# com-uart.net
KiCad netlist of a schematic drawn in EAGLE
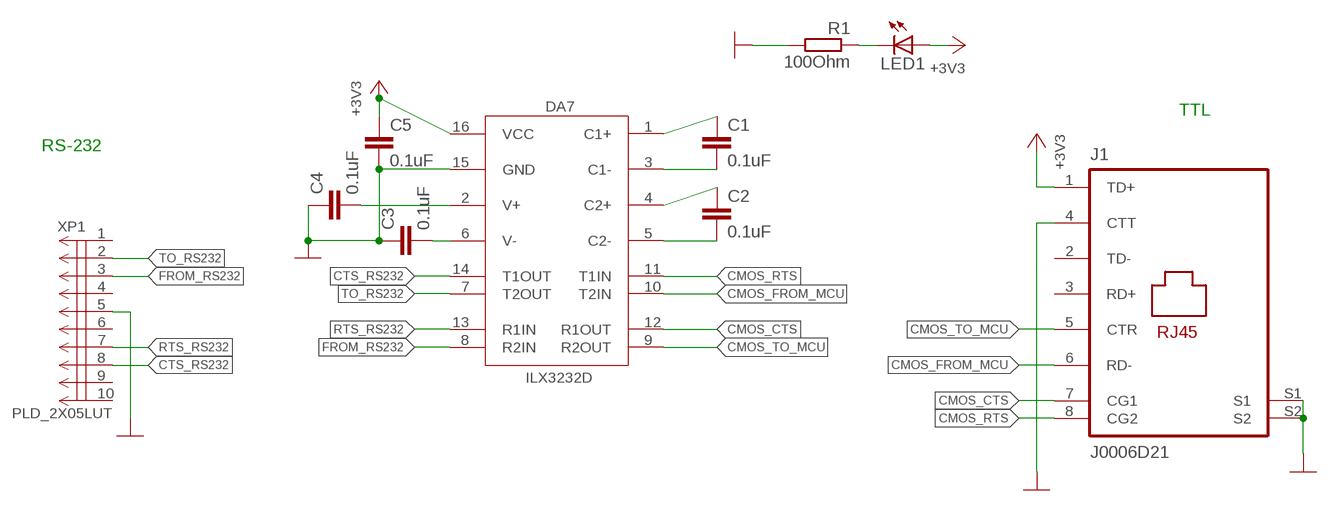
[diagram p0: schematic, sheet 1]

(export (version "E")
  (design (tool "Eeschema 10.0.6"))
  (components
    (comp (ref "C1")
      (value "0.1uF")
      (footprint "eagle-import:0805")
      (fields (field (name "PARTNO") "?"))
      (libsource (lib "eagle-import") (part "CAP0805"))
    )
    (comp (ref "C2")
      (value "0.1uF")
      (footprint "eagle-import:0805")
      (fields (field (name "PARTNO") "?"))
      (libsource (lib "eagle-import") (part "CAP0805"))
    )
    (comp (ref "C3")
      (value "0.1uF")
      (footprint "eagle-import:0805")
      (fields (field (name "PARTNO") "?"))
      (libsource (lib "eagle-import") (part "CAP0805"))
    )
    (comp (ref "C4")
      (value "0.1uF")
      (footprint "eagle-import:0805")
      (fields (field (name "PARTNO") "?"))
      (libsource (lib "eagle-import") (part "CAP0805"))
    )
    (comp (ref "C5")
      (value "0.1uF")
      (footprint "eagle-import:0805")
      (fields (field (name "PARTNO") "?"))
      (libsource (lib "eagle-import") (part "CAP0805"))
    )
    (comp (ref "DA7")
      (value "ILX3232D")
      (footprint "eagle-import:SO16")
      (libsource (lib "eagle-import") (part "ILX3232D"))
    )
    (comp (ref "J1")
      (value "J0006D21")
      (footprint "eagle-import:J0-C_D_E")
      (libsource (lib "eagle-import") (part "J0006D21"))
    )
    (comp (ref "LED1")
      (value "LED3MM")
      (footprint "eagle-import:LED3MM")
      (libsource (lib "eagle-import") (part "LED3MM"))
    )
    (comp (ref "R1")
      (value "100Ohm")
      (footprint "eagle-import:0805")
      (libsource (lib "eagle-import") (part "RESISTOR0805"))
    )
    (comp (ref "XP1")
      (value "PLD_2X05LUT")
      (footprint "eagle-import:PLD_2X05_LUT")
      (libsource (lib "eagle-import") (part "PLD_2X05LUT"))
    )
  )
  (nets
    (net (code "1") (name "+3V3") (class "Default")
      (node (ref "C5") (pin "1") (pinfunction "1_1") (pintype "passive"))
      (node (ref "DA7") (pin "16") (pinfunction "VCC_16") (pintype "power_in"))
      (node (ref "J1") (pin "1") (pinfunction "TD+_1") (pintype "passive"))
      (node (ref "LED1") (pin "A") (pinfunction "A_A") (pintype "passive"))
    )
    (net (code "2") (name "CMOS_CTS") (class "Default")
      (node (ref "DA7") (pin "12") (pinfunction "R1OUT_12") (pintype "output"))
      (node (ref "J1") (pin "7") (pinfunction "CG1_7") (pintype "passive"))
    )
    (net (code "3") (name "CMOS_FROM_MCU") (class "Default")
      (node (ref "DA7") (pin "10") (pinfunction "T2IN_10") (pintype "input"))
      (node (ref "J1") (pin "6") (pinfunction "RD-_6") (pintype "passive"))
    )
    (net (code "4") (name "CMOS_RTS") (class "Default")
      (node (ref "DA7") (pin "11") (pinfunction "T1IN_11") (pintype "input"))
      (node (ref "J1") (pin "8") (pinfunction "CG2_8") (pintype "passive"))
    )
    (net (code "5") (name "CMOS_TO_MCU") (class "Default")
      (node (ref "DA7") (pin "9") (pinfunction "R2OUT_9") (pintype "output"))
      (node (ref "J1") (pin "5") (pinfunction "CTR_5") (pintype "passive"))
    )
    (net (code "6") (name "CTS_RS232") (class "Default")
      (node (ref "DA7") (pin "14") (pinfunction "T1OUT_14") (pintype "output"))
      (node (ref "XP1") (pin "8") (pinfunction "8_8") (pintype "passive"))
    )
    (net (code "7") (name "FROM_RS232") (class "Default")
      (node (ref "DA7") (pin "8") (pinfunction "R2IN_8") (pintype "input"))
      (node (ref "XP1") (pin "3") (pinfunction "3_3") (pintype "passive"))
    )
    (net (code "8") (name "GND") (class "Default")
      (node (ref "C3") (pin "1") (pinfunction "1_1") (pintype "passive"))
      (node (ref "C4") (pin "1") (pinfunction "1_1") (pintype "passive"))
      (node (ref "C5") (pin "2") (pinfunction "2_2") (pintype "passive"))
      (node (ref "DA7") (pin "15") (pinfunction "GND_15") (pintype "power_in"))
      (node (ref "J1") (pin "4") (pinfunction "CTT_4") (pintype "passive"))
      (node (ref "J1") (pin "S1") (pinfunction "S1_S1") (pintype "passive"))
      (node (ref "J1") (pin "S2") (pinfunction "S2_S2") (pintype "passive"))
      (node (ref "R1") (pin "2") (pinfunction "2_2") (pintype "passive"))
      (node (ref "XP1") (pin "5") (pinfunction "5_5") (pintype "passive"))
    )
    (net (code "9") (name "Net-(DA7-C1+)") (class "Default")
      (node (ref "C1") (pin "1") (pinfunction "1_1") (pintype "passive"))
      (node (ref "DA7") (pin "1") (pinfunction "C1+_1") (pintype "passive"))
    )
    (net (code "10") (name "Net-(DA7-C1-)") (class "Default")
      (node (ref "C1") (pin "2") (pinfunction "2_2") (pintype "passive"))
      (node (ref "DA7") (pin "3") (pinfunction "C1-_3") (pintype "passive"))
    )
    (net (code "11") (name "Net-(DA7-C2+)") (class "Default")
      (node (ref "C2") (pin "1") (pinfunction "1_1") (pintype "passive"))
      (node (ref "DA7") (pin "4") (pinfunction "C2+_4") (pintype "passive"))
    )
    (net (code "12") (name "Net-(DA7-C2-)") (class "Default")
      (node (ref "C2") (pin "2") (pinfunction "2_2") (pintype "passive"))
      (node (ref "DA7") (pin "5") (pinfunction "C2-_5") (pintype "passive"))
    )
    (net (code "13") (name "Net-(DA7-V+)") (class "Default")
      (node (ref "C4") (pin "2") (pinfunction "2_2") (pintype "passive"))
      (node (ref "DA7") (pin "2") (pinfunction "V+_2") (pintype "passive"))
    )
    (net (code "14") (name "Net-(DA7-V-)") (class "Default")
      (node (ref "C3") (pin "2") (pinfunction "2_2") (pintype "passive"))
      (node (ref "DA7") (pin "6") (pinfunction "V-_6") (pintype "passive"))
    )
    (net (code "15") (name "Net-(LED1-C)") (class "Default")
      (node (ref "LED1") (pin "K") (pinfunction "C_K") (pintype "passive"))
      (node (ref "R1") (pin "1") (pinfunction "1_1") (pintype "passive"))
    )
    (net (code "16") (name "RTS_RS232") (class "Default")
      (node (ref "DA7") (pin "13") (pinfunction "R1IN_13") (pintype "input"))
      (node (ref "XP1") (pin "7") (pinfunction "7_7") (pintype "passive"))
    )
    (net (code "17") (name "TO_RS232") (class "Default")
      (node (ref "DA7") (pin "7") (pinfunction "T2OUT_7") (pintype "output"))
      (node (ref "XP1") (pin "2") (pinfunction "2_2") (pintype "passive"))
    )
    (net (code "18") (name "unconnected-(J1-RD+-Pad3)") (class "Default")
      (node (ref "J1") (pin "3") (pinfunction "RD+_3") (pintype "passive"))
    )
    (net (code "19") (name "unconnected-(J1-TD--Pad2)") (class "Default")
      (node (ref "J1") (pin "2") (pinfunction "TD-_2") (pintype "passive"))
    )
    (net (code "20") (name "unconnected-(XP1-Pad1)") (class "Default")
      (node (ref "XP1") (pin "1") (pinfunction "1_1") (pintype "passive"))
    )
    (net (code "21") (name "unconnected-(XP1-Pad4)") (class "Default")
      (node (ref "XP1") (pin "4") (pinfunction "4_4") (pintype "passive"))
    )
    (net (code "22") (name "unconnected-(XP1-Pad6)") (class "Default")
      (node (ref "XP1") (pin "6") (pinfunction "6_6") (pintype "passive"))
    )
    (net (code "23") (name "unconnected-(XP1-Pad9)") (class "Default")
      (node (ref "XP1") (pin "9") (pinfunction "9_9") (pintype "passive"))
    )
    (net (code "24") (name "unconnected-(XP1-Pad10)") (class "Default")
      (node (ref "XP1") (pin "10") (pinfunction "10_10") (pintype "passive"))
    )
  )
)
